# RPi_Stepper_Hat_V1_0.net
KiCad netlist of a schematic drawn in Altium Designer
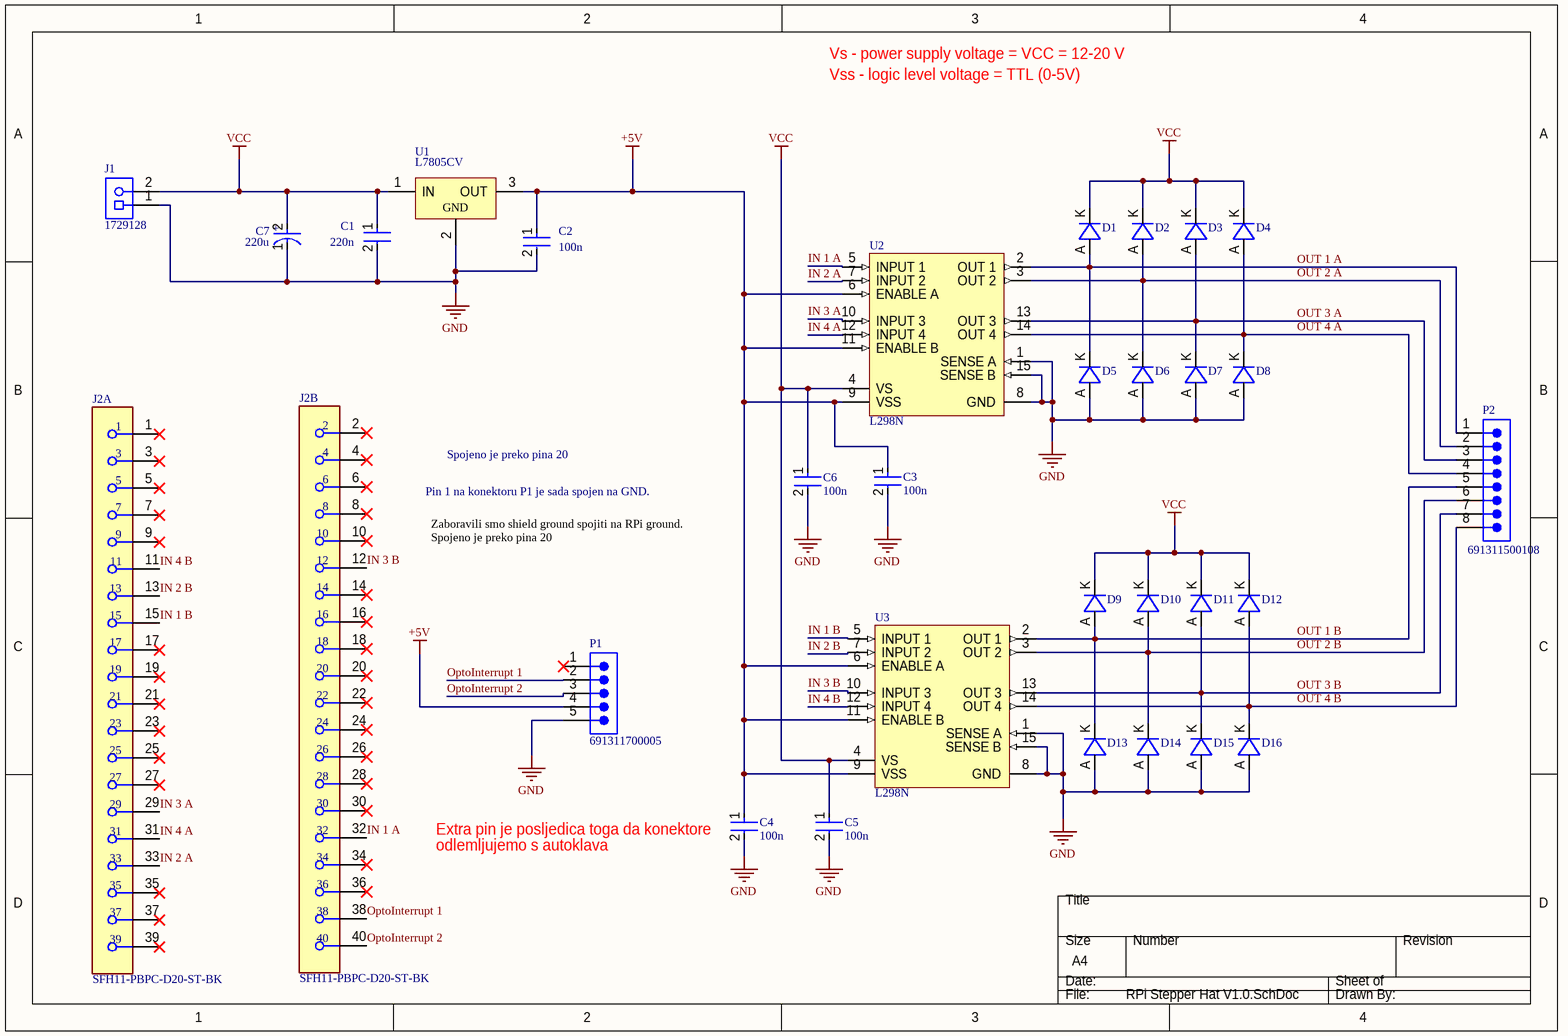
[diagram p0: RPi Stepper Hat V1.0.SchDoc]

(export (version "E")
  (design (tool "Eeschema 10.0.6"))
  (components
    (comp (ref "C1")
      (value "220n")
      (footprint "FP-RCE1K1-2_5-MFG")
      (description "Cap Ceramic Monolithic 220nF 50V 10% Thru-Hole Bulk RCER71H224K1M1H03A")
      (fields (field (name "TOLERANCE") "10%"))
      (libsource (lib "Altium Content Vault") (part "02cd4be3c70576c341d710602a673aa"))
    )
    (comp (ref "C2")
      (value "100n")
      (footprint "FP-RDE0P1-MFG")
      (description "Ceramic Capacitor 100nF ±10% 25V X7R Radial RDER71E104K0S1H03A")
      (fields (field (name "TOLERANCE") "10%"))
      (libsource (lib "Altium Content Vault") (part "b4654b650e69147ec39a6b967a45e02"))
    )
    (comp (ref "C3")
      (value "100n")
      (footprint "FP-RDE0P1-MFG")
      (description "Ceramic Capacitor 100nF ±10% 25V X7R Radial RDER71E104K0S1H03A")
      (fields (field (name "TOLERANCE") "10%"))
      (libsource (lib "Altium Content Vault") (part "b4654b650e69147ec39a6b967a45e02"))
    )
    (comp (ref "C4")
      (value "100n")
      (footprint "FP-RDE0P1-MFG")
      (description "Ceramic Capacitor 100nF ±10% 25V X7R Radial RDER71E104K0S1H03A")
      (fields (field (name "TOLERANCE") "10%"))
      (libsource (lib "Altium Content Vault") (part "b4654b650e69147ec39a6b967a45e02"))
    )
    (comp (ref "C5")
      (value "100n")
      (footprint "FP-RDE0P1-MFG")
      (description "Ceramic Capacitor 100nF ±10% 25V X7R Radial RDER71E104K0S1H03A")
      (fields (field (name "TOLERANCE") "10%"))
      (libsource (lib "Altium Content Vault") (part "b4654b650e69147ec39a6b967a45e02"))
    )
    (comp (ref "C6")
      (value "100n")
      (footprint "FP-RDE0P1-MFG")
      (description "Ceramic Capacitor 100nF ±10% 25V X7R Radial RDER71E104K0S1H03A")
      (fields (field (name "TOLERANCE") "10%"))
      (libsource (lib "Altium Content Vault") (part "b4654b650e69147ec39a6b967a45e02"))
    )
    (comp (ref "C7")
      (value "220u")
      (footprint "FP-RAD-TH-D_10_0_5-L_25_2-MFG")
      (description "Aluminum Electrolytic Capacitors (Radial Lead Type) 220uF ±20% 63V EEUFR1J221LB")
      (fields (field (name "TOLERANCE") "20%"))
      (libsource (lib "Altium Content Vault") (part "a00bbbee19879c290e62620ae7e47b1"))
    )
    (comp (ref "D1")
      (value "RFN2VWM2STR")
      (footprint "DIOM4326X24N")
      (libsource (lib "RPi Stepper Hat V1.0 SchLib") (part "RFN2VWM2STR"))
    )
    (comp (ref "D2")
      (value "RFN2VWM2STR")
      (footprint "DIOM4326X24N")
      (libsource (lib "RPi Stepper Hat V1.0 SchLib") (part "RFN2VWM2STR"))
    )
    (comp (ref "D3")
      (value "RFN2VWM2STR")
      (footprint "DIOM4326X24N")
      (libsource (lib "RPi Stepper Hat V1.0 SchLib") (part "RFN2VWM2STR"))
    )
    (comp (ref "D4")
      (value "RFN2VWM2STR")
      (footprint "DIOM4326X24N")
      (libsource (lib "RPi Stepper Hat V1.0 SchLib") (part "RFN2VWM2STR"))
    )
    (comp (ref "D5")
      (value "RFN2VWM2STR")
      (footprint "DIOM4326X24N")
      (libsource (lib "RPi Stepper Hat V1.0 SchLib") (part "RFN2VWM2STR"))
    )
    (comp (ref "D6")
      (value "RFN2VWM2STR")
      (footprint "DIOM4326X24N")
      (libsource (lib "RPi Stepper Hat V1.0 SchLib") (part "RFN2VWM2STR"))
    )
    (comp (ref "D7")
      (value "RFN2VWM2STR")
      (footprint "DIOM4326X24N")
      (libsource (lib "RPi Stepper Hat V1.0 SchLib") (part "RFN2VWM2STR"))
    )
    (comp (ref "D8")
      (value "RFN2VWM2STR")
      (footprint "DIOM4326X24N")
      (libsource (lib "RPi Stepper Hat V1.0 SchLib") (part "RFN2VWM2STR"))
    )
    (comp (ref "D9")
      (value "RFN2VWM2STR")
      (footprint "DIOM4326X24N")
      (libsource (lib "RPi Stepper Hat V1.0 SchLib") (part "RFN2VWM2STR"))
    )
    (comp (ref "D10")
      (value "RFN2VWM2STR")
      (footprint "DIOM4326X24N")
      (libsource (lib "RPi Stepper Hat V1.0 SchLib") (part "RFN2VWM2STR"))
    )
    (comp (ref "D11")
      (value "RFN2VWM2STR")
      (footprint "DIOM4326X24N")
      (libsource (lib "RPi Stepper Hat V1.0 SchLib") (part "RFN2VWM2STR"))
    )
    (comp (ref "D12")
      (value "RFN2VWM2STR")
      (footprint "DIOM4326X24N")
      (libsource (lib "RPi Stepper Hat V1.0 SchLib") (part "RFN2VWM2STR"))
    )
    (comp (ref "D13")
      (value "RFN2VWM2STR")
      (footprint "DIOM4326X24N")
      (libsource (lib "RPi Stepper Hat V1.0 SchLib") (part "RFN2VWM2STR"))
    )
    (comp (ref "D14")
      (value "RFN2VWM2STR")
      (footprint "DIOM4326X24N")
      (libsource (lib "RPi Stepper Hat V1.0 SchLib") (part "RFN2VWM2STR"))
    )
    (comp (ref "D15")
      (value "RFN2VWM2STR")
      (footprint "DIOM4326X24N")
      (libsource (lib "RPi Stepper Hat V1.0 SchLib") (part "RFN2VWM2STR"))
    )
    (comp (ref "D16")
      (value "RFN2VWM2STR")
      (footprint "DIOM4326X24N")
      (libsource (lib "RPi Stepper Hat V1.0 SchLib") (part "RFN2VWM2STR"))
    )
    (comp (ref "J1")
      (value "1729128")
      (footprint "PHOE-1729128-2_V")
      (description "PCB Terminal Block, 13.5 A, 400 V, 2-Pin THD, RoHS, Bulk")
      (fields (field (name "MANUFACTURER") "Phoenix Contact"))
      (libsource (lib "Altium Content Vault") (part "CN-2P-F-R2"))
    )
    (comp (ref "J2")
      (value "SFH11-PBPC-D20-ST-BK")
      (footprint "FP-SFH11-PBPC-D20-ST-BK-MFG")
      (description "CONN HDR 40POS 0.1 GOLD PCB")
      (libsource (lib "Altium Content Vault") (part "7acf1c4a8db21028d11741a46a6ec78"))
    )
    (comp (ref "P1")
      (value "691311700005")
      (footprint "691311700005")
      (fields (field (name "VOLTAGE") "300V"))
      (libsource (lib "Altium Content Vault") (part "TBL - 1R - 05P - Male"))
    )
    (comp (ref "P2")
      (value "691311500108")
      (footprint "691311500108")
      (fields (field (name "VOLTAGE") "300V"))
      (libsource (lib "Altium Content Vault") (part "TBL - 1R - 08P - Male"))
    )
    (comp (ref "U1")
      (value "L7805CV")
      (footprint "TO220")
      (description "Positive Voltage Regulator, 5V, 3-Pin TO-220")
      (libsource (lib "Altium Content Vault") (part "PM-REG-L4940-SIL3"))
    )
    (comp (ref "U2")
      (value "L298N")
      (footprint "STM-FM-15")
      (description "Dual Full-Bridge Driver, 4.8 to 46 V, -40 to 150 degC, 15-Pin FM (MW 15L), RoHS, Tube")
      (fields (field (name "MANUFACTURER") "STMicroelectronics") (field (name "PARTNUMBER") "L298"))
      (libsource (lib "Altium Content Vault") (part "STM-L298-15"))
    )
    (comp (ref "U3")
      (value "L298N")
      (footprint "STM-FM-15")
      (description "Dual Full-Bridge Driver, 4.8 to 46 V, -40 to 150 degC, 15-Pin FM (MW 15L), RoHS, Tube")
      (fields (field (name "MANUFACTURER") "STMicroelectronics") (field (name "PARTNUMBER") "L298"))
      (libsource (lib "Altium Content Vault") (part "STM-L298-15"))
    )
  )
  (nets
    (net (code "1") (name "+5V") (class "Default")
      (node (ref "C2") (pin "1") (pinfunction "1_1") (pintype "passive"))
      (node (ref "C3") (pin "1") (pinfunction "1_1") (pintype "passive"))
      (node (ref "C4") (pin "1") (pinfunction "1_1") (pintype "passive"))
      (node (ref "P1") (pin "4") (pinfunction "4_4") (pintype "passive"))
      (node (ref "U1") (pin "3") (pinfunction "OUT_3") (pintype "power_in"))
      (node (ref "U2") (pin "11") (pinfunction "ENABLE_B_11") (pintype "input"))
      (node (ref "U2") (pin "6") (pinfunction "ENABLE_A_6") (pintype "input"))
      (node (ref "U2") (pin "9") (pinfunction "VSS_9") (pintype "power_in"))
      (node (ref "U3") (pin "11") (pinfunction "ENABLE_B_11") (pintype "input"))
      (node (ref "U3") (pin "6") (pinfunction "ENABLE_A_6") (pintype "input"))
      (node (ref "U3") (pin "9") (pinfunction "VSS_9") (pintype "power_in"))
    )
    (net (code "2") (name "/IN 1 A") (class "Default")
      (node (ref "J2") (pin "32") (pinfunction "32_32") (pintype "passive"))
      (node (ref "U2") (pin "5") (pinfunction "INPUT_1_5") (pintype "input"))
    )
    (net (code "3") (name "/IN 1 B") (class "Default")
      (node (ref "J2") (pin "15") (pinfunction "15_15") (pintype "passive"))
      (node (ref "U3") (pin "5") (pinfunction "INPUT_1_5") (pintype "input"))
    )
    (net (code "4") (name "/IN 2 A") (class "Default")
      (node (ref "J2") (pin "33") (pinfunction "33_33") (pintype "passive"))
      (node (ref "U2") (pin "7") (pinfunction "INPUT_2_7") (pintype "input"))
    )
    (net (code "5") (name "/IN 2 B") (class "Default")
      (node (ref "J2") (pin "13") (pinfunction "13_13") (pintype "passive"))
      (node (ref "U3") (pin "7") (pinfunction "INPUT_2_7") (pintype "input"))
    )
    (net (code "6") (name "/IN 3 A") (class "Default")
      (node (ref "J2") (pin "29") (pinfunction "29_29") (pintype "passive"))
      (node (ref "U2") (pin "10") (pinfunction "INPUT_3_10") (pintype "input"))
    )
    (net (code "7") (name "/IN 3 B") (class "Default")
      (node (ref "J2") (pin "12") (pinfunction "12_12") (pintype "passive"))
      (node (ref "U3") (pin "10") (pinfunction "INPUT_3_10") (pintype "input"))
    )
    (net (code "8") (name "/IN 4 A") (class "Default")
      (node (ref "J2") (pin "31") (pinfunction "31_31") (pintype "passive"))
      (node (ref "U2") (pin "12") (pinfunction "INPUT_4_12") (pintype "input"))
    )
    (net (code "9") (name "/IN 4 B") (class "Default")
      (node (ref "J2") (pin "11") (pinfunction "11_11") (pintype "passive"))
      (node (ref "U3") (pin "12") (pinfunction "INPUT_4_12") (pintype "input"))
    )
    (net (code "10") (name "/OUT 1 A") (class "Default")
      (node (ref "D1") (pin "A") (pinfunction "anode_A") (pintype "passive"))
      (node (ref "D5") (pin "K") (pinfunction "cathode_K") (pintype "passive"))
      (node (ref "P2") (pin "1") (pinfunction "1_1") (pintype "passive"))
      (node (ref "U2") (pin "2") (pinfunction "OUT_1_2") (pintype "output"))
    )
    (net (code "11") (name "/OUT 1 B") (class "Default")
      (node (ref "D13") (pin "K") (pinfunction "cathode_K") (pintype "passive"))
      (node (ref "D9") (pin "A") (pinfunction "anode_A") (pintype "passive"))
      (node (ref "P2") (pin "5") (pinfunction "5_5") (pintype "passive"))
      (node (ref "U3") (pin "2") (pinfunction "OUT_1_2") (pintype "output"))
    )
    (net (code "12") (name "/OUT 2 A") (class "Default")
      (node (ref "D2") (pin "A") (pinfunction "anode_A") (pintype "passive"))
      (node (ref "D6") (pin "K") (pinfunction "cathode_K") (pintype "passive"))
      (node (ref "P2") (pin "2") (pinfunction "2_2") (pintype "passive"))
      (node (ref "U2") (pin "3") (pinfunction "OUT_2_3") (pintype "output"))
    )
    (net (code "13") (name "/OUT 2 B") (class "Default")
      (node (ref "D10") (pin "A") (pinfunction "anode_A") (pintype "passive"))
      (node (ref "D14") (pin "K") (pinfunction "cathode_K") (pintype "passive"))
      (node (ref "P2") (pin "6") (pinfunction "6_6") (pintype "passive"))
      (node (ref "U3") (pin "3") (pinfunction "OUT_2_3") (pintype "output"))
    )
    (net (code "14") (name "/OUT 3 A") (class "Default")
      (node (ref "D3") (pin "A") (pinfunction "anode_A") (pintype "passive"))
      (node (ref "D7") (pin "K") (pinfunction "cathode_K") (pintype "passive"))
      (node (ref "P2") (pin "3") (pinfunction "3_3") (pintype "passive"))
      (node (ref "U2") (pin "13") (pinfunction "OUT_3_13") (pintype "output"))
    )
    (net (code "15") (name "/OUT 3 B") (class "Default")
      (node (ref "D11") (pin "A") (pinfunction "anode_A") (pintype "passive"))
      (node (ref "D15") (pin "K") (pinfunction "cathode_K") (pintype "passive"))
      (node (ref "P2") (pin "7") (pinfunction "7_7") (pintype "passive"))
      (node (ref "U3") (pin "13") (pinfunction "OUT_3_13") (pintype "output"))
    )
    (net (code "16") (name "/OUT 4 A") (class "Default")
      (node (ref "D4") (pin "A") (pinfunction "anode_A") (pintype "passive"))
      (node (ref "D8") (pin "K") (pinfunction "cathode_K") (pintype "passive"))
      (node (ref "P2") (pin "4") (pinfunction "4_4") (pintype "passive"))
      (node (ref "U2") (pin "14") (pinfunction "OUT_4_14") (pintype "output"))
    )
    (net (code "17") (name "/OUT 4 B") (class "Default")
      (node (ref "D12") (pin "A") (pinfunction "anode_A") (pintype "passive"))
      (node (ref "D16") (pin "K") (pinfunction "cathode_K") (pintype "passive"))
      (node (ref "P2") (pin "8") (pinfunction "8_8") (pintype "passive"))
      (node (ref "U3") (pin "14") (pinfunction "OUT_4_14") (pintype "output"))
    )
    (net (code "18") (name "/OptoInterrupt 1") (class "Default")
      (node (ref "J2") (pin "38") (pinfunction "38_38") (pintype "passive"))
      (node (ref "P1") (pin "2") (pinfunction "2_2") (pintype "passive"))
    )
    (net (code "19") (name "/OptoInterrupt 2") (class "Default")
      (node (ref "J2") (pin "40") (pinfunction "40_40") (pintype "passive"))
      (node (ref "P1") (pin "3") (pinfunction "3_3") (pintype "passive"))
    )
    (net (code "20") (name "GND") (class "Default")
      (node (ref "C1") (pin "2") (pinfunction "2_2") (pintype "passive"))
      (node (ref "C2") (pin "2") (pinfunction "2_2") (pintype "passive"))
      (node (ref "C3") (pin "2") (pinfunction "2_2") (pintype "passive"))
      (node (ref "C4") (pin "2") (pinfunction "2_2") (pintype "passive"))
      (node (ref "C5") (pin "2") (pinfunction "2_2") (pintype "passive"))
      (node (ref "C6") (pin "2") (pinfunction "2_2") (pintype "passive"))
      (node (ref "C7") (pin "1") (pinfunction "C_1") (pintype "passive"))
      (node (ref "D13") (pin "A") (pinfunction "anode_A") (pintype "passive"))
      (node (ref "D14") (pin "A") (pinfunction "anode_A") (pintype "passive"))
      (node (ref "D15") (pin "A") (pinfunction "anode_A") (pintype "passive"))
      (node (ref "D16") (pin "A") (pinfunction "anode_A") (pintype "passive"))
      (node (ref "D5") (pin "A") (pinfunction "anode_A") (pintype "passive"))
      (node (ref "D6") (pin "A") (pinfunction "anode_A") (pintype "passive"))
      (node (ref "D7") (pin "A") (pinfunction "anode_A") (pintype "passive"))
      (node (ref "D8") (pin "A") (pinfunction "anode_A") (pintype "passive"))
      (node (ref "J1") (pin "1") (pinfunction "1_1") (pintype "passive"))
      (node (ref "P1") (pin "5") (pinfunction "5_5") (pintype "passive"))
      (node (ref "U1") (pin "2") (pinfunction "GND_2") (pintype "power_in"))
      (node (ref "U2") (pin "1") (pinfunction "SENSE_A_1") (pintype "input"))
      (node (ref "U2") (pin "15") (pinfunction "SENSE_B_15") (pintype "input"))
      (node (ref "U2") (pin "8") (pinfunction "GND_8") (pintype "power_in"))
      (node (ref "U3") (pin "1") (pinfunction "SENSE_A_1") (pintype "input"))
      (node (ref "U3") (pin "15") (pinfunction "SENSE_B_15") (pintype "input"))
      (node (ref "U3") (pin "8") (pinfunction "GND_8") (pintype "power_in"))
    )
    (net (code "21") (name "VCC") (class "Default")
      (node (ref "C1") (pin "1") (pinfunction "1_1") (pintype "passive"))
      (node (ref "C5") (pin "1") (pinfunction "1_1") (pintype "passive"))
      (node (ref "C6") (pin "1") (pinfunction "1_1") (pintype "passive"))
      (node (ref "C7") (pin "2") (pinfunction "A_2") (pintype "passive"))
      (node (ref "D1") (pin "K") (pinfunction "cathode_K") (pintype "passive"))
      (node (ref "D10") (pin "K") (pinfunction "cathode_K") (pintype "passive"))
      (node (ref "D11") (pin "K") (pinfunction "cathode_K") (pintype "passive"))
      (node (ref "D12") (pin "K") (pinfunction "cathode_K") (pintype "passive"))
      (node (ref "D2") (pin "K") (pinfunction "cathode_K") (pintype "passive"))
      (node (ref "D3") (pin "K") (pinfunction "cathode_K") (pintype "passive"))
      (node (ref "D4") (pin "K") (pinfunction "cathode_K") (pintype "passive"))
      (node (ref "D9") (pin "K") (pinfunction "cathode_K") (pintype "passive"))
      (node (ref "J1") (pin "2") (pinfunction "2_2") (pintype "passive"))
      (node (ref "U1") (pin "1") (pinfunction "IN_1") (pintype "power_in"))
      (node (ref "U2") (pin "4") (pinfunction "VS_4") (pintype "power_in"))
      (node (ref "U3") (pin "4") (pinfunction "VS_4") (pintype "power_in"))
    )
    (net (code "22") (name "unconnected-(J2-Pad1)") (class "Default")
      (node (ref "J2") (pin "1") (pinfunction "1_1") (pintype "passive+no_connect"))
    )
    (net (code "23") (name "unconnected-(J2-Pad2)") (class "Default")
      (node (ref "J2") (pin "2") (pinfunction "2_2") (pintype "passive+no_connect"))
    )
    (net (code "24") (name "unconnected-(J2-Pad3)") (class "Default")
      (node (ref "J2") (pin "3") (pinfunction "3_3") (pintype "passive+no_connect"))
    )
    (net (code "25") (name "unconnected-(J2-Pad4)") (class "Default")
      (node (ref "J2") (pin "4") (pinfunction "4_4") (pintype "passive+no_connect"))
    )
    (net (code "26") (name "unconnected-(J2-Pad5)") (class "Default")
      (node (ref "J2") (pin "5") (pinfunction "5_5") (pintype "passive+no_connect"))
    )
    (net (code "27") (name "unconnected-(J2-Pad6)") (class "Default")
      (node (ref "J2") (pin "6") (pinfunction "6_6") (pintype "passive+no_connect"))
    )
    (net (code "28") (name "unconnected-(J2-Pad7)") (class "Default")
      (node (ref "J2") (pin "7") (pinfunction "7_7") (pintype "passive+no_connect"))
    )
    (net (code "29") (name "unconnected-(J2-Pad8)") (class "Default")
      (node (ref "J2") (pin "8") (pinfunction "8_8") (pintype "passive+no_connect"))
    )
    (net (code "30") (name "unconnected-(J2-Pad9)") (class "Default")
      (node (ref "J2") (pin "9") (pinfunction "9_9") (pintype "passive+no_connect"))
    )
    (net (code "31") (name "unconnected-(J2-Pad10)") (class "Default")
      (node (ref "J2") (pin "10") (pinfunction "10_10") (pintype "passive+no_connect"))
    )
    (net (code "32") (name "unconnected-(J2-Pad14)") (class "Default")
      (node (ref "J2") (pin "14") (pinfunction "14_14") (pintype "passive+no_connect"))
    )
    (net (code "33") (name "unconnected-(J2-Pad16)") (class "Default")
      (node (ref "J2") (pin "16") (pinfunction "16_16") (pintype "passive+no_connect"))
    )
    (net (code "34") (name "unconnected-(J2-Pad17)") (class "Default")
      (node (ref "J2") (pin "17") (pinfunction "17_17") (pintype "passive+no_connect"))
    )
    (net (code "35") (name "unconnected-(J2-Pad18)") (class "Default")
      (node (ref "J2") (pin "18") (pinfunction "18_18") (pintype "passive+no_connect"))
    )
    (net (code "36") (name "unconnected-(J2-Pad19)") (class "Default")
      (node (ref "J2") (pin "19") (pinfunction "19_19") (pintype "passive+no_connect"))
    )
    (net (code "37") (name "unconnected-(J2-Pad20)") (class "Default")
      (node (ref "J2") (pin "20") (pinfunction "20_20") (pintype "passive+no_connect"))
    )
    (net (code "38") (name "unconnected-(J2-Pad21)") (class "Default")
      (node (ref "J2") (pin "21") (pinfunction "21_21") (pintype "passive+no_connect"))
    )
    (net (code "39") (name "unconnected-(J2-Pad22)") (class "Default")
      (node (ref "J2") (pin "22") (pinfunction "22_22") (pintype "passive+no_connect"))
    )
    (net (code "40") (name "unconnected-(J2-Pad23)") (class "Default")
      (node (ref "J2") (pin "23") (pinfunction "23_23") (pintype "passive+no_connect"))
    )
    (net (code "41") (name "unconnected-(J2-Pad24)") (class "Default")
      (node (ref "J2") (pin "24") (pinfunction "24_24") (pintype "passive+no_connect"))
    )
    (net (code "42") (name "unconnected-(J2-Pad25)") (class "Default")
      (node (ref "J2") (pin "25") (pinfunction "25_25") (pintype "passive+no_connect"))
    )
    (net (code "43") (name "unconnected-(J2-Pad26)") (class "Default")
      (node (ref "J2") (pin "26") (pinfunction "26_26") (pintype "passive+no_connect"))
    )
    (net (code "44") (name "unconnected-(J2-Pad27)") (class "Default")
      (node (ref "J2") (pin "27") (pinfunction "27_27") (pintype "passive+no_connect"))
    )
    (net (code "45") (name "unconnected-(J2-Pad28)") (class "Default")
      (node (ref "J2") (pin "28") (pinfunction "28_28") (pintype "passive+no_connect"))
    )
    (net (code "46") (name "unconnected-(J2-Pad30)") (class "Default")
      (node (ref "J2") (pin "30") (pinfunction "30_30") (pintype "passive+no_connect"))
    )
    (net (code "47") (name "unconnected-(J2-Pad34)") (class "Default")
      (node (ref "J2") (pin "34") (pinfunction "34_34") (pintype "passive+no_connect"))
    )
    (net (code "48") (name "unconnected-(J2-Pad35)") (class "Default")
      (node (ref "J2") (pin "35") (pinfunction "35_35") (pintype "passive+no_connect"))
    )
    (net (code "49") (name "unconnected-(J2-Pad36)") (class "Default")
      (node (ref "J2") (pin "36") (pinfunction "36_36") (pintype "passive+no_connect"))
    )
    (net (code "50") (name "unconnected-(J2-Pad37)") (class "Default")
      (node (ref "J2") (pin "37") (pinfunction "37_37") (pintype "passive+no_connect"))
    )
    (net (code "51") (name "unconnected-(J2-Pad39)") (class "Default")
      (node (ref "J2") (pin "39") (pinfunction "39_39") (pintype "passive+no_connect"))
    )
    (net (code "52") (name "unconnected-(P1-Pad1)") (class "Default")
      (node (ref "P1") (pin "1") (pinfunction "1_1") (pintype "passive+no_connect"))
    )
  )
)
